# thedeck.net
KiCad netlist of a schematic drawn in EasyEDA Pro
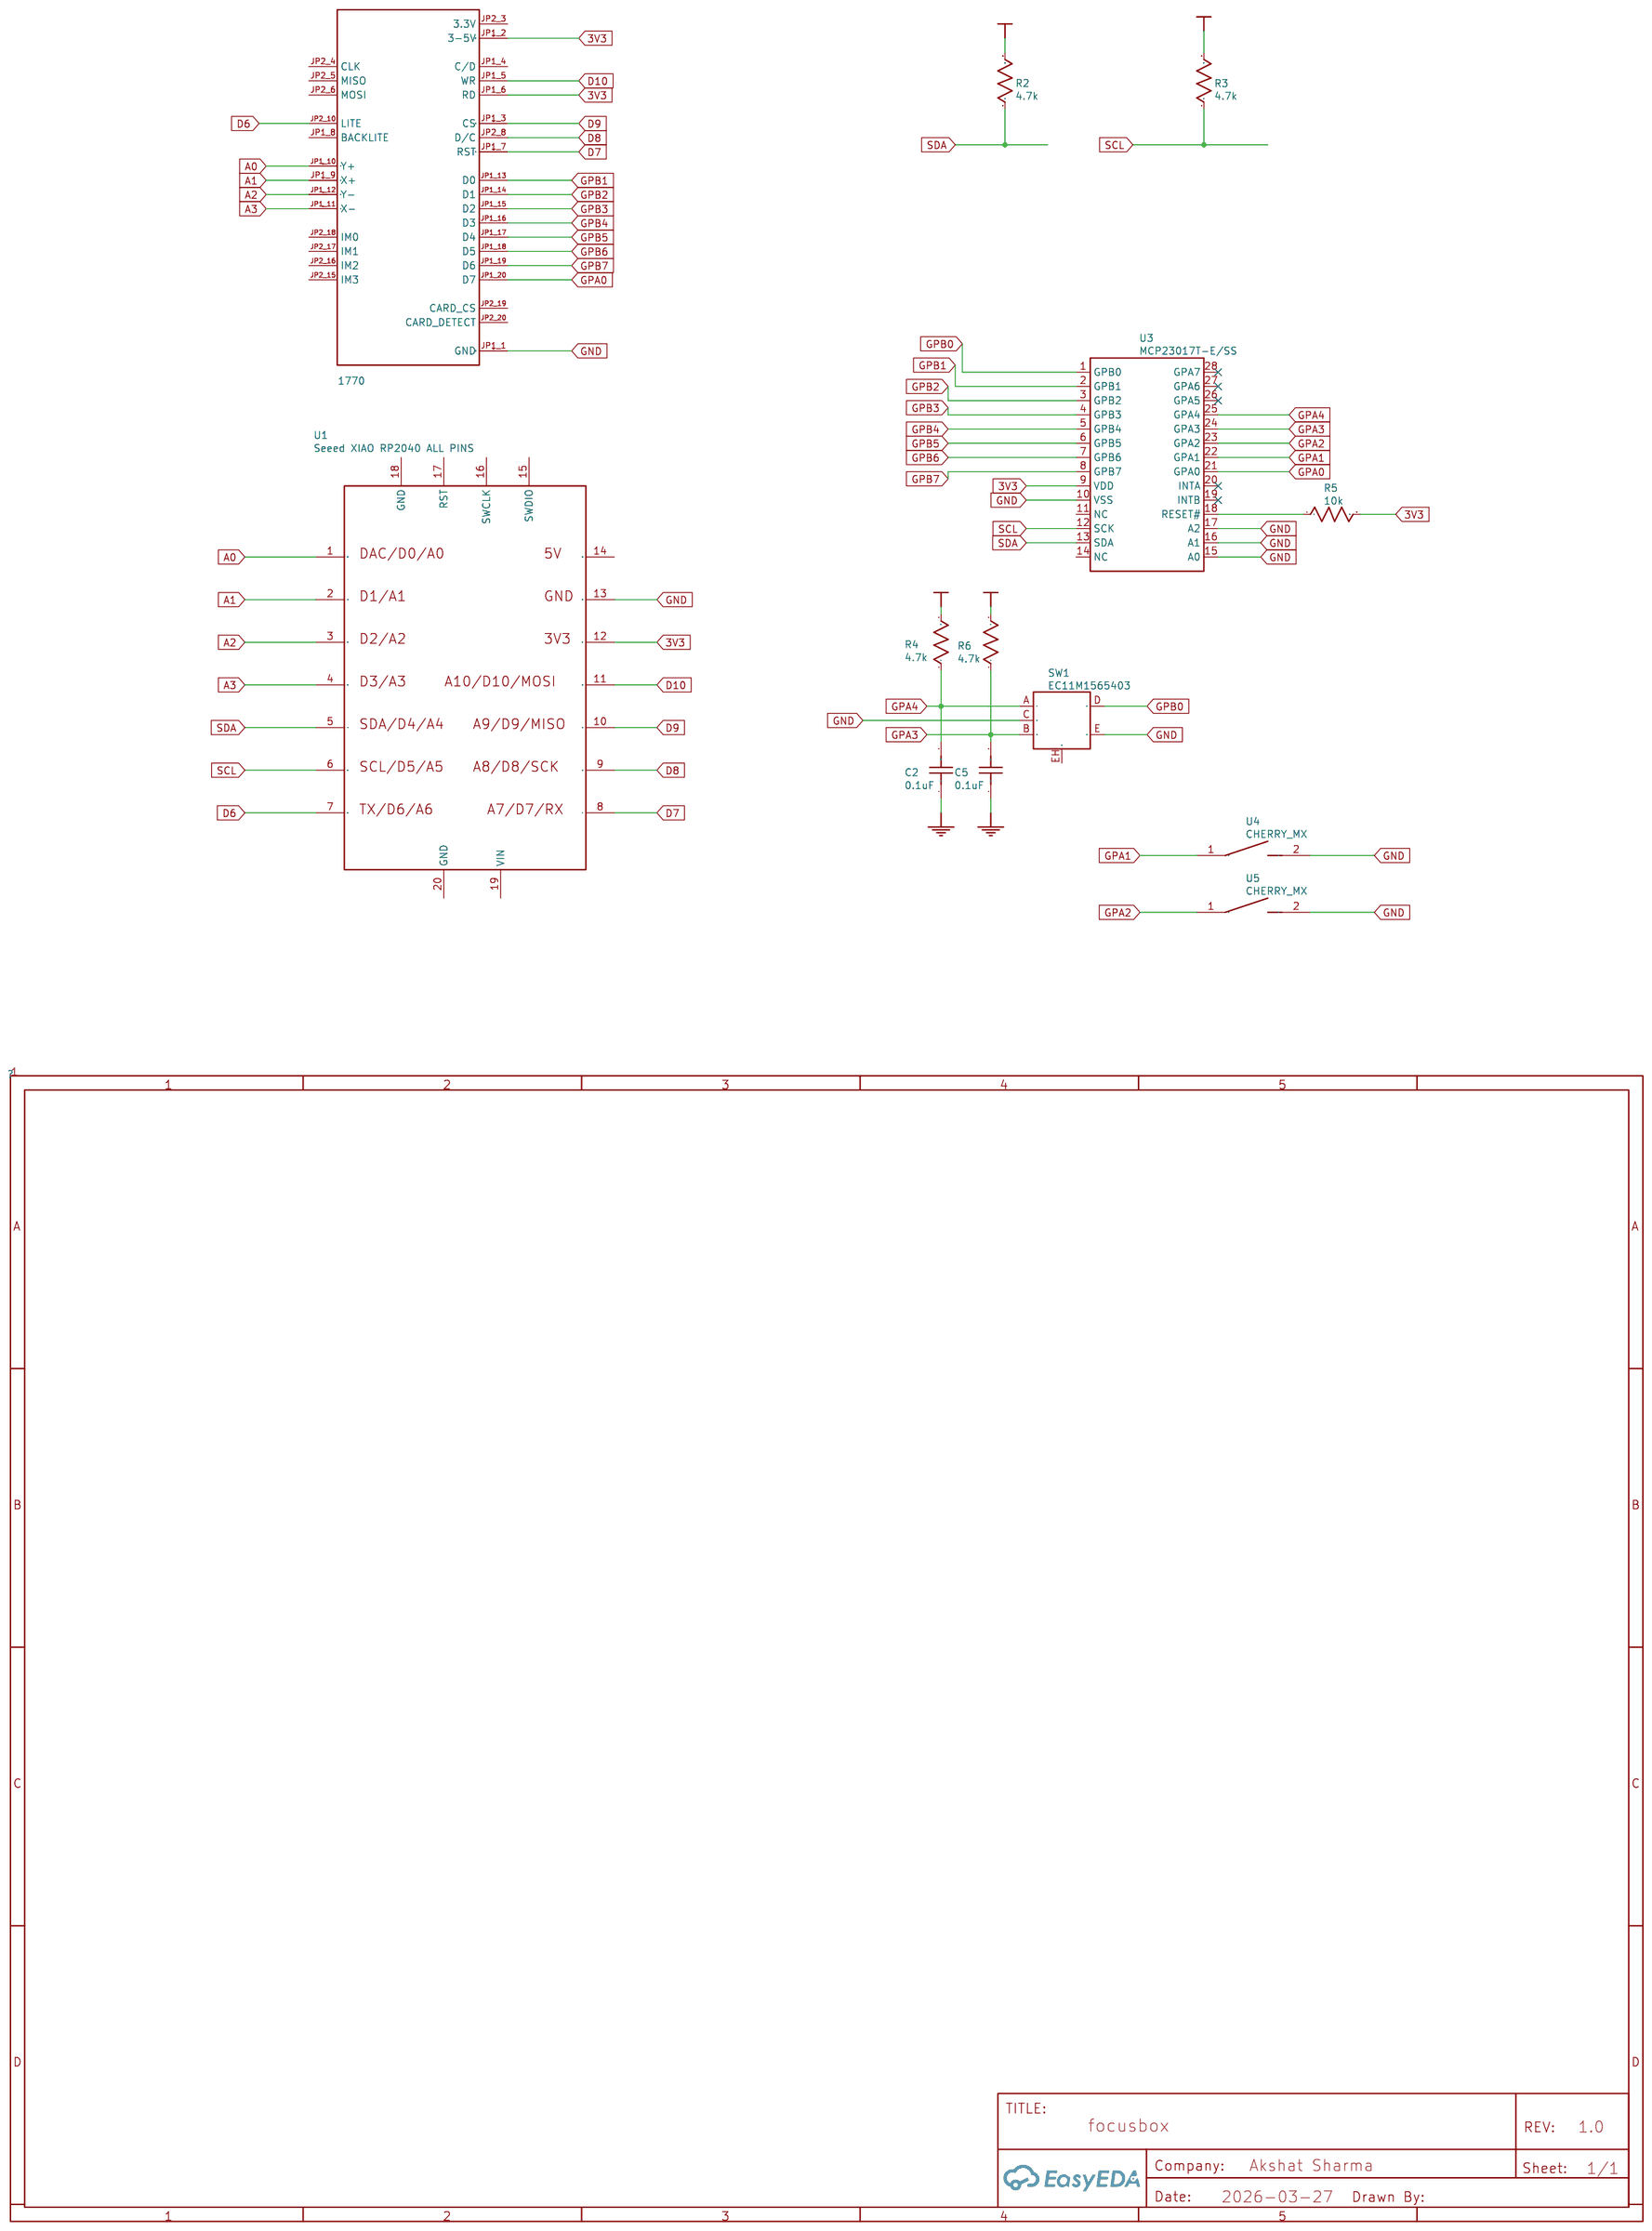
[diagram p0: schematic sheet]

(export (version "E")
  (design (tool "Eeschema 10.0.6"))
  (components
    (comp (ref "C2")
      (value "0.1uF")
      (footprint "easyedapro:C0603")
      (fields (field (name "Contributor") "LCEDA_Lib"))
      (libsource (lib "easyedapro") (part "0.1uF"))
    )
    (comp (ref "C5")
      (value "0.1uF")
      (footprint "easyedapro:C0603")
      (fields (field (name "Contributor") "LCEDA_Lib"))
      (libsource (lib "easyedapro") (part "0.1uF"))
    )
    (comp (ref "R2")
      (value "4.7k")
      (footprint "easyedapro:R0603")
      (fields (field (name "Contributor") "LCEDA_Lib"))
      (libsource (lib "easyedapro") (part "4.7k"))
    )
    (comp (ref "R3")
      (value "4.7k")
      (footprint "easyedapro:R0603")
      (fields (field (name "Contributor") "LCEDA_Lib"))
      (libsource (lib "easyedapro") (part "4.7k"))
    )
    (comp (ref "R4")
      (value "4.7k")
      (footprint "easyedapro:R0603")
      (fields (field (name "Contributor") "LCEDA_Lib"))
      (libsource (lib "easyedapro") (part "4.7k"))
    )
    (comp (ref "R5")
      (value "10k")
      (footprint "easyedapro:R0603")
      (fields (field (name "Contributor") "LCEDA_Lib"))
      (libsource (lib "easyedapro") (part "10k"))
    )
    (comp (ref "R6")
      (value "4.7k")
      (footprint "easyedapro:R0603")
      (fields (field (name "Contributor") "LCEDA_Lib"))
      (libsource (lib "easyedapro") (part "4.7k"))
    )
    (comp (ref "SW1")
      (value "EC11M1565403")
      (footprint "easyedapro:SW-TH_EC11M1565403")
      (fields (field (name "Manufacturer") "ALPSALPINE(阿尔卑斯阿尔派)") (field (name "Contributor") "LCSC"))
      (libsource (lib "easyedapro") (part "EC11M1565403"))
    )
    (comp (ref "U1")
      (value "Seeed XIAO RP2040 ALL PINS")
      (footprint "easyedapro:SEEED XIAO RP2040")
      (fields
        (field (name "Manufacturer Part") "102010328")
        (field (name "Manufacturer") "Seeedstudio")
        (field (name "Contributor") "Derick2k")
      )
      (libsource (lib "easyedapro") (part "Seeed XIAO RP2040 ALL PINS"))
    )
    (comp (ref "U3")
      (value "MCP23017T-E/SS")
      (footprint "easyedapro:SSOP-28_L10.2-W5.3-P0.65-LS7.8-BL")
      (fields (field (name "Manufacturer") "MICROCHIP(美国微芯)") (field (name "Contributor") "lcsc"))
      (libsource (lib "easyedapro") (part "MCP23017T-E/SS"))
    )
    (comp (ref "U4")
      (value "CHERRY_MX")
      (footprint "easyedapro:CHERRY MX")
      (fields (field (name "Manufacturer Part") "CHERRY") (field (name "Contributor") "drummdan"))
      (libsource (lib "easyedapro") (part "CHERRY_MX"))
    )
    (comp (ref "U5")
      (value "CHERRY_MX")
      (footprint "easyedapro:CHERRY MX")
      (fields (field (name "Manufacturer Part") "CHERRY") (field (name "Contributor") "drummdan"))
      (libsource (lib "easyedapro") (part "CHERRY_MX"))
    )
    (comp (ref "U7") (value "1770") (libsource (lib "easyedapro") (part "1770")))
  )
  (nets
    (net (code "1") (name "3V3") (class "Default")
      (node (ref "R2") (pin "2") (pinfunction "2_2") (pintype "unspecified"))
      (node (ref "R3") (pin "2") (pinfunction "2_2") (pintype "unspecified"))
      (node (ref "R4") (pin "2") (pinfunction "2_2") (pintype "unspecified"))
      (node (ref "R5") (pin "2") (pinfunction "2_2") (pintype "unspecified"))
      (node (ref "R6") (pin "2") (pinfunction "2_2") (pintype "unspecified"))
      (node (ref "U1") (pin "12") (pinfunction "11_12") (pintype "unspecified"))
      (node (ref "U3") (pin "9") (pinfunction "VDD_9") (pintype "unspecified"))
      (node (ref "U7") (pin "JP1_2") (pinfunction "3-5V_JP1_2") (pintype "unspecified"))
      (node (ref "U7") (pin "JP1_6") (pinfunction "RD_JP1_6") (pintype "unspecified"))
      (node (ref "U7") (pin "JP2_2") (pinfunction "3-5V_JP2_2") (pintype "unspecified"))
    )
    (net (code "2") (name "A0") (class "Default")
      (node (ref "U1") (pin "1") (pinfunction "0_1") (pintype "unspecified"))
      (node (ref "U7") (pin "JP1_10") (pinfunction "Y+_JP1_10") (pintype "unspecified"))
      (node (ref "U7") (pin "JP2_11") (pinfunction "Y+_JP2_11") (pintype "unspecified"))
    )
    (net (code "3") (name "A1") (class "Default")
      (node (ref "U1") (pin "2") (pinfunction "1_2") (pintype "unspecified"))
      (node (ref "U7") (pin "JP1_9") (pinfunction "X+_JP1_9") (pintype "unspecified"))
      (node (ref "U7") (pin "JP2_12") (pinfunction "X+_JP2_12") (pintype "unspecified"))
    )
    (net (code "4") (name "A2") (class "Default")
      (node (ref "U1") (pin "3") (pinfunction "2_3") (pintype "unspecified"))
      (node (ref "U7") (pin "JP1_12") (pinfunction "Y-_JP1_12") (pintype "unspecified"))
      (node (ref "U7") (pin "JP2_13") (pinfunction "Y-_JP2_13") (pintype "unspecified"))
    )
    (net (code "5") (name "A3") (class "Default")
      (node (ref "U1") (pin "4") (pinfunction "3_4") (pintype "unspecified"))
      (node (ref "U7") (pin "JP1_11") (pinfunction "X-_JP1_11") (pintype "unspecified"))
      (node (ref "U7") (pin "JP2_14") (pinfunction "X-_JP2_14") (pintype "unspecified"))
    )
    (net (code "6") (name "D6") (class "Default")
      (node (ref "U1") (pin "7") (pinfunction "6_7") (pintype "unspecified"))
      (node (ref "U7") (pin "JP2_10") (pinfunction "LITE_JP2_10") (pintype "input"))
    )
    (net (code "7") (name "D7") (class "Default")
      (node (ref "U1") (pin "8") (pinfunction "7_8") (pintype "unspecified"))
      (node (ref "U7") (pin "JP1_7") (pinfunction "RST_JP1_7") (pintype "unspecified"))
      (node (ref "U7") (pin "JP2_9") (pinfunction "RST_JP2_9") (pintype "unspecified"))
    )
    (net (code "8") (name "D8") (class "Default")
      (node (ref "U1") (pin "9") (pinfunction "8_9") (pintype "unspecified"))
      (node (ref "U7") (pin "JP2_8") (pinfunction "D/C_JP2_8") (pintype "unspecified"))
    )
    (net (code "9") (name "D9") (class "Default")
      (node (ref "U1") (pin "10") (pinfunction "9_10") (pintype "unspecified"))
      (node (ref "U7") (pin "JP1_3") (pinfunction "CS_JP1_3") (pintype "unspecified"))
      (node (ref "U7") (pin "JP2_7") (pinfunction "CS_JP2_7") (pintype "unspecified"))
    )
    (net (code "10") (name "D10") (class "Default")
      (node (ref "U1") (pin "11") (pinfunction "10_11") (pintype "unspecified"))
      (node (ref "U7") (pin "JP1_5") (pinfunction "WR_JP1_5") (pintype "unspecified"))
    )
    (net (code "11") (name "GND") (class "Default")
      (node (ref "C2") (pin "1") (pinfunction "1_1") (pintype "unspecified"))
      (node (ref "C5") (pin "1") (pinfunction "1_1") (pintype "unspecified"))
      (node (ref "SW1") (pin "C") (pinfunction "C_C") (pintype "unspecified"))
      (node (ref "SW1") (pin "E") (pinfunction "E_E") (pintype "unspecified"))
      (node (ref "U1") (pin "13") (pinfunction "12_13") (pintype "unspecified"))
      (node (ref "U3") (pin "10") (pinfunction "VSS_10") (pintype "unspecified"))
      (node (ref "U3") (pin "15") (pinfunction "A0_15") (pintype "unspecified"))
      (node (ref "U3") (pin "16") (pinfunction "A1_16") (pintype "unspecified"))
      (node (ref "U3") (pin "17") (pinfunction "A2_17") (pintype "unspecified"))
      (node (ref "U4") (pin "2") (pinfunction "2_2") (pintype "unspecified"))
      (node (ref "U5") (pin "2") (pinfunction "2_2") (pintype "unspecified"))
      (node (ref "U7") (pin "JP1_1") (pinfunction "GND_JP1_1") (pintype "unspecified"))
      (node (ref "U7") (pin "JP2_1") (pinfunction "GND_JP2_1") (pintype "unspecified"))
    )
    (net (code "12") (name "GPA0") (class "Default")
      (node (ref "U3") (pin "21") (pinfunction "GPA0_21") (pintype "unspecified"))
      (node (ref "U7") (pin "JP1_20") (pinfunction "D7_JP1_20") (pintype "unspecified"))
    )
    (net (code "13") (name "GPA1") (class "Default")
      (node (ref "U3") (pin "22") (pinfunction "GPA1_22") (pintype "unspecified"))
      (node (ref "U4") (pin "1") (pinfunction "1_1") (pintype "unspecified"))
    )
    (net (code "14") (name "GPA2") (class "Default")
      (node (ref "U3") (pin "23") (pinfunction "GPA2_23") (pintype "unspecified"))
      (node (ref "U5") (pin "1") (pinfunction "1_1") (pintype "unspecified"))
    )
    (net (code "15") (name "GPA3") (class "Default")
      (node (ref "C5") (pin "2") (pinfunction "2_2") (pintype "unspecified"))
      (node (ref "R6") (pin "1") (pinfunction "1_1") (pintype "unspecified"))
      (node (ref "SW1") (pin "B") (pinfunction "B_B") (pintype "unspecified"))
      (node (ref "U3") (pin "24") (pinfunction "GPA3_24") (pintype "unspecified"))
    )
    (net (code "16") (name "GPA4") (class "Default")
      (node (ref "C2") (pin "2") (pinfunction "2_2") (pintype "unspecified"))
      (node (ref "R4") (pin "1") (pinfunction "1_1") (pintype "unspecified"))
      (node (ref "SW1") (pin "A") (pinfunction "A_A") (pintype "unspecified"))
      (node (ref "U3") (pin "25") (pinfunction "GPA4_25") (pintype "unspecified"))
    )
    (net (code "17") (name "GPB0") (class "Default")
      (node (ref "SW1") (pin "D") (pinfunction "D_D") (pintype "unspecified"))
      (node (ref "U3") (pin "1") (pinfunction "GPB0_1") (pintype "unspecified"))
    )
    (net (code "18") (name "GPB1") (class "Default")
      (node (ref "U3") (pin "2") (pinfunction "GPB1_2") (pintype "unspecified"))
      (node (ref "U7") (pin "JP1_13") (pinfunction "D0_JP1_13") (pintype "unspecified"))
    )
    (net (code "19") (name "GPB2") (class "Default")
      (node (ref "U3") (pin "3") (pinfunction "GPB2_3") (pintype "unspecified"))
      (node (ref "U7") (pin "JP1_14") (pinfunction "D1_JP1_14") (pintype "unspecified"))
    )
    (net (code "20") (name "GPB3") (class "Default")
      (node (ref "U3") (pin "4") (pinfunction "GPB3_4") (pintype "unspecified"))
      (node (ref "U7") (pin "JP1_15") (pinfunction "D2_JP1_15") (pintype "unspecified"))
    )
    (net (code "21") (name "GPB4") (class "Default")
      (node (ref "U3") (pin "5") (pinfunction "GPB4_5") (pintype "unspecified"))
      (node (ref "U7") (pin "JP1_16") (pinfunction "D3_JP1_16") (pintype "unspecified"))
    )
    (net (code "22") (name "GPB5") (class "Default")
      (node (ref "U3") (pin "6") (pinfunction "GPB5_6") (pintype "unspecified"))
      (node (ref "U7") (pin "JP1_17") (pinfunction "D4_JP1_17") (pintype "unspecified"))
    )
    (net (code "23") (name "GPB6") (class "Default")
      (node (ref "U3") (pin "7") (pinfunction "GPB6_7") (pintype "unspecified"))
      (node (ref "U7") (pin "JP1_18") (pinfunction "D5_JP1_18") (pintype "unspecified"))
    )
    (net (code "24") (name "GPB7") (class "Default")
      (node (ref "U3") (pin "8") (pinfunction "GPB7_8") (pintype "unspecified"))
      (node (ref "U7") (pin "JP1_19") (pinfunction "D6_JP1_19") (pintype "unspecified"))
    )
    (net (code "25") (name "Net-(U3-RESET#)") (class "Default")
      (node (ref "R5") (pin "1") (pinfunction "1_1") (pintype "unspecified"))
      (node (ref "U3") (pin "18") (pinfunction "RESET#_18") (pintype "unspecified"))
    )
    (net (code "26") (name "SCL") (class "Default")
      (node (ref "R3") (pin "1") (pinfunction "1_1") (pintype "unspecified"))
      (node (ref "U1") (pin "6") (pinfunction "5_6") (pintype "unspecified"))
      (node (ref "U3") (pin "12") (pinfunction "SCK_12") (pintype "unspecified"))
    )
    (net (code "27") (name "SDA") (class "Default")
      (node (ref "R2") (pin "1") (pinfunction "1_1") (pintype "unspecified"))
      (node (ref "U1") (pin "5") (pinfunction "4_5") (pintype "unspecified"))
      (node (ref "U3") (pin "13") (pinfunction "SDA_13") (pintype "unspecified"))
    )
    (net (code "28") (name "unconnected-(SW1-PadEH)") (class "Default")
      (node (ref "SW1") (pin "EH") (pinfunction "EH_EH") (pintype "unspecified"))
    )
    (net (code "29") (name "unconnected-(U1-13-Pad14)") (class "Default")
      (node (ref "U1") (pin "14") (pinfunction "13_14") (pintype "unspecified"))
    )
    (net (code "30") (name "unconnected-(U1-GND-Pad18)") (class "Default")
      (node (ref "U1") (pin "18") (pinfunction "GND_18") (pintype "unspecified"))
    )
    (net (code "31") (name "unconnected-(U1-GND-Pad20)") (class "Default")
      (node (ref "U1") (pin "20") (pinfunction "GND_20") (pintype "unspecified"))
    )
    (net (code "32") (name "unconnected-(U1-RST-Pad17)") (class "Default")
      (node (ref "U1") (pin "17") (pinfunction "RST_17") (pintype "unspecified"))
    )
    (net (code "33") (name "unconnected-(U1-SWCLK-Pad16)") (class "Default")
      (node (ref "U1") (pin "16") (pinfunction "SWCLK_16") (pintype "unspecified"))
    )
    (net (code "34") (name "unconnected-(U1-SWDIO-Pad15)") (class "Default")
      (node (ref "U1") (pin "15") (pinfunction "SWDIO_15") (pintype "unspecified"))
    )
    (net (code "35") (name "unconnected-(U1-VIN-Pad19)") (class "Default")
      (node (ref "U1") (pin "19") (pinfunction "VIN_19") (pintype "unspecified"))
    )
    (net (code "36") (name "unconnected-(U3-GPA5-Pad26)") (class "Default")
      (node (ref "U3") (pin "26") (pinfunction "GPA5_26") (pintype "unspecified+no_connect"))
    )
    (net (code "37") (name "unconnected-(U3-GPA6-Pad27)") (class "Default")
      (node (ref "U3") (pin "27") (pinfunction "GPA6_27") (pintype "unspecified+no_connect"))
    )
    (net (code "38") (name "unconnected-(U3-GPA7-Pad28)") (class "Default")
      (node (ref "U3") (pin "28") (pinfunction "GPA7_28") (pintype "unspecified+no_connect"))
    )
    (net (code "39") (name "unconnected-(U3-INTA-Pad20)") (class "Default")
      (node (ref "U3") (pin "20") (pinfunction "INTA_20") (pintype "unspecified+no_connect"))
    )
    (net (code "40") (name "unconnected-(U3-INTB-Pad19)") (class "Default")
      (node (ref "U3") (pin "19") (pinfunction "INTB_19") (pintype "unspecified+no_connect"))
    )
    (net (code "41") (name "unconnected-(U3-NC-Pad11)") (class "Default")
      (node (ref "U3") (pin "11") (pinfunction "NC_11") (pintype "unspecified"))
    )
    (net (code "42") (name "unconnected-(U3-NC-Pad14)") (class "Default")
      (node (ref "U3") (pin "14") (pinfunction "NC_14") (pintype "unspecified"))
    )
    (net (code "43") (name "unconnected-(U7-3.3V-PadJP2_3)") (class "Default")
      (node (ref "U7") (pin "JP2_3") (pinfunction "3.3V_JP2_3") (pintype "unspecified"))
    )
    (net (code "44") (name "unconnected-(U7-BACKLITE-PadJP1_8)") (class "Default")
      (node (ref "U7") (pin "JP1_8") (pinfunction "BACKLITE_JP1_8") (pintype "input"))
    )
    (net (code "45") (name "unconnected-(U7-CARD_CS-PadJP2_19)") (class "Default")
      (node (ref "U7") (pin "JP2_19") (pinfunction "CARD_CS_JP2_19") (pintype "unspecified"))
    )
    (net (code "46") (name "unconnected-(U7-CARD_DETECT-PadJP2_20)") (class "Default")
      (node (ref "U7") (pin "JP2_20") (pinfunction "CARD_DETECT_JP2_20") (pintype "unspecified"))
    )
    (net (code "47") (name "unconnected-(U7-CLK-PadJP2_4)") (class "Default")
      (node (ref "U7") (pin "JP2_4") (pinfunction "CLK_JP2_4") (pintype "input"))
    )
    (net (code "48") (name "unconnected-(U7-C{slash}D-PadJP1_4)") (class "Default")
      (node (ref "U7") (pin "JP1_4") (pinfunction "C/D_JP1_4") (pintype "unspecified"))
    )
    (net (code "49") (name "unconnected-(U7-IM0-PadJP2_18)") (class "Default")
      (node (ref "U7") (pin "JP2_18") (pinfunction "IM0_JP2_18") (pintype "unspecified"))
    )
    (net (code "50") (name "unconnected-(U7-IM1-PadJP2_17)") (class "Default")
      (node (ref "U7") (pin "JP2_17") (pinfunction "IM1_JP2_17") (pintype "unspecified"))
    )
    (net (code "51") (name "unconnected-(U7-IM2-PadJP2_16)") (class "Default")
      (node (ref "U7") (pin "JP2_16") (pinfunction "IM2_JP2_16") (pintype "unspecified"))
    )
    (net (code "52") (name "unconnected-(U7-IM3-PadJP2_15)") (class "Default")
      (node (ref "U7") (pin "JP2_15") (pinfunction "IM3_JP2_15") (pintype "unspecified"))
    )
    (net (code "53") (name "unconnected-(U7-MISO-PadJP2_5)") (class "Default")
      (node (ref "U7") (pin "JP2_5") (pinfunction "MISO_JP2_5") (pintype "output"))
    )
    (net (code "54") (name "unconnected-(U7-MOSI-PadJP2_6)") (class "Default")
      (node (ref "U7") (pin "JP2_6") (pinfunction "MOSI_JP2_6") (pintype "input"))
    )
  )
)
